# DAC_LED_Monitor.net
KiCad netlist of a schematic drawn in Altium Designer
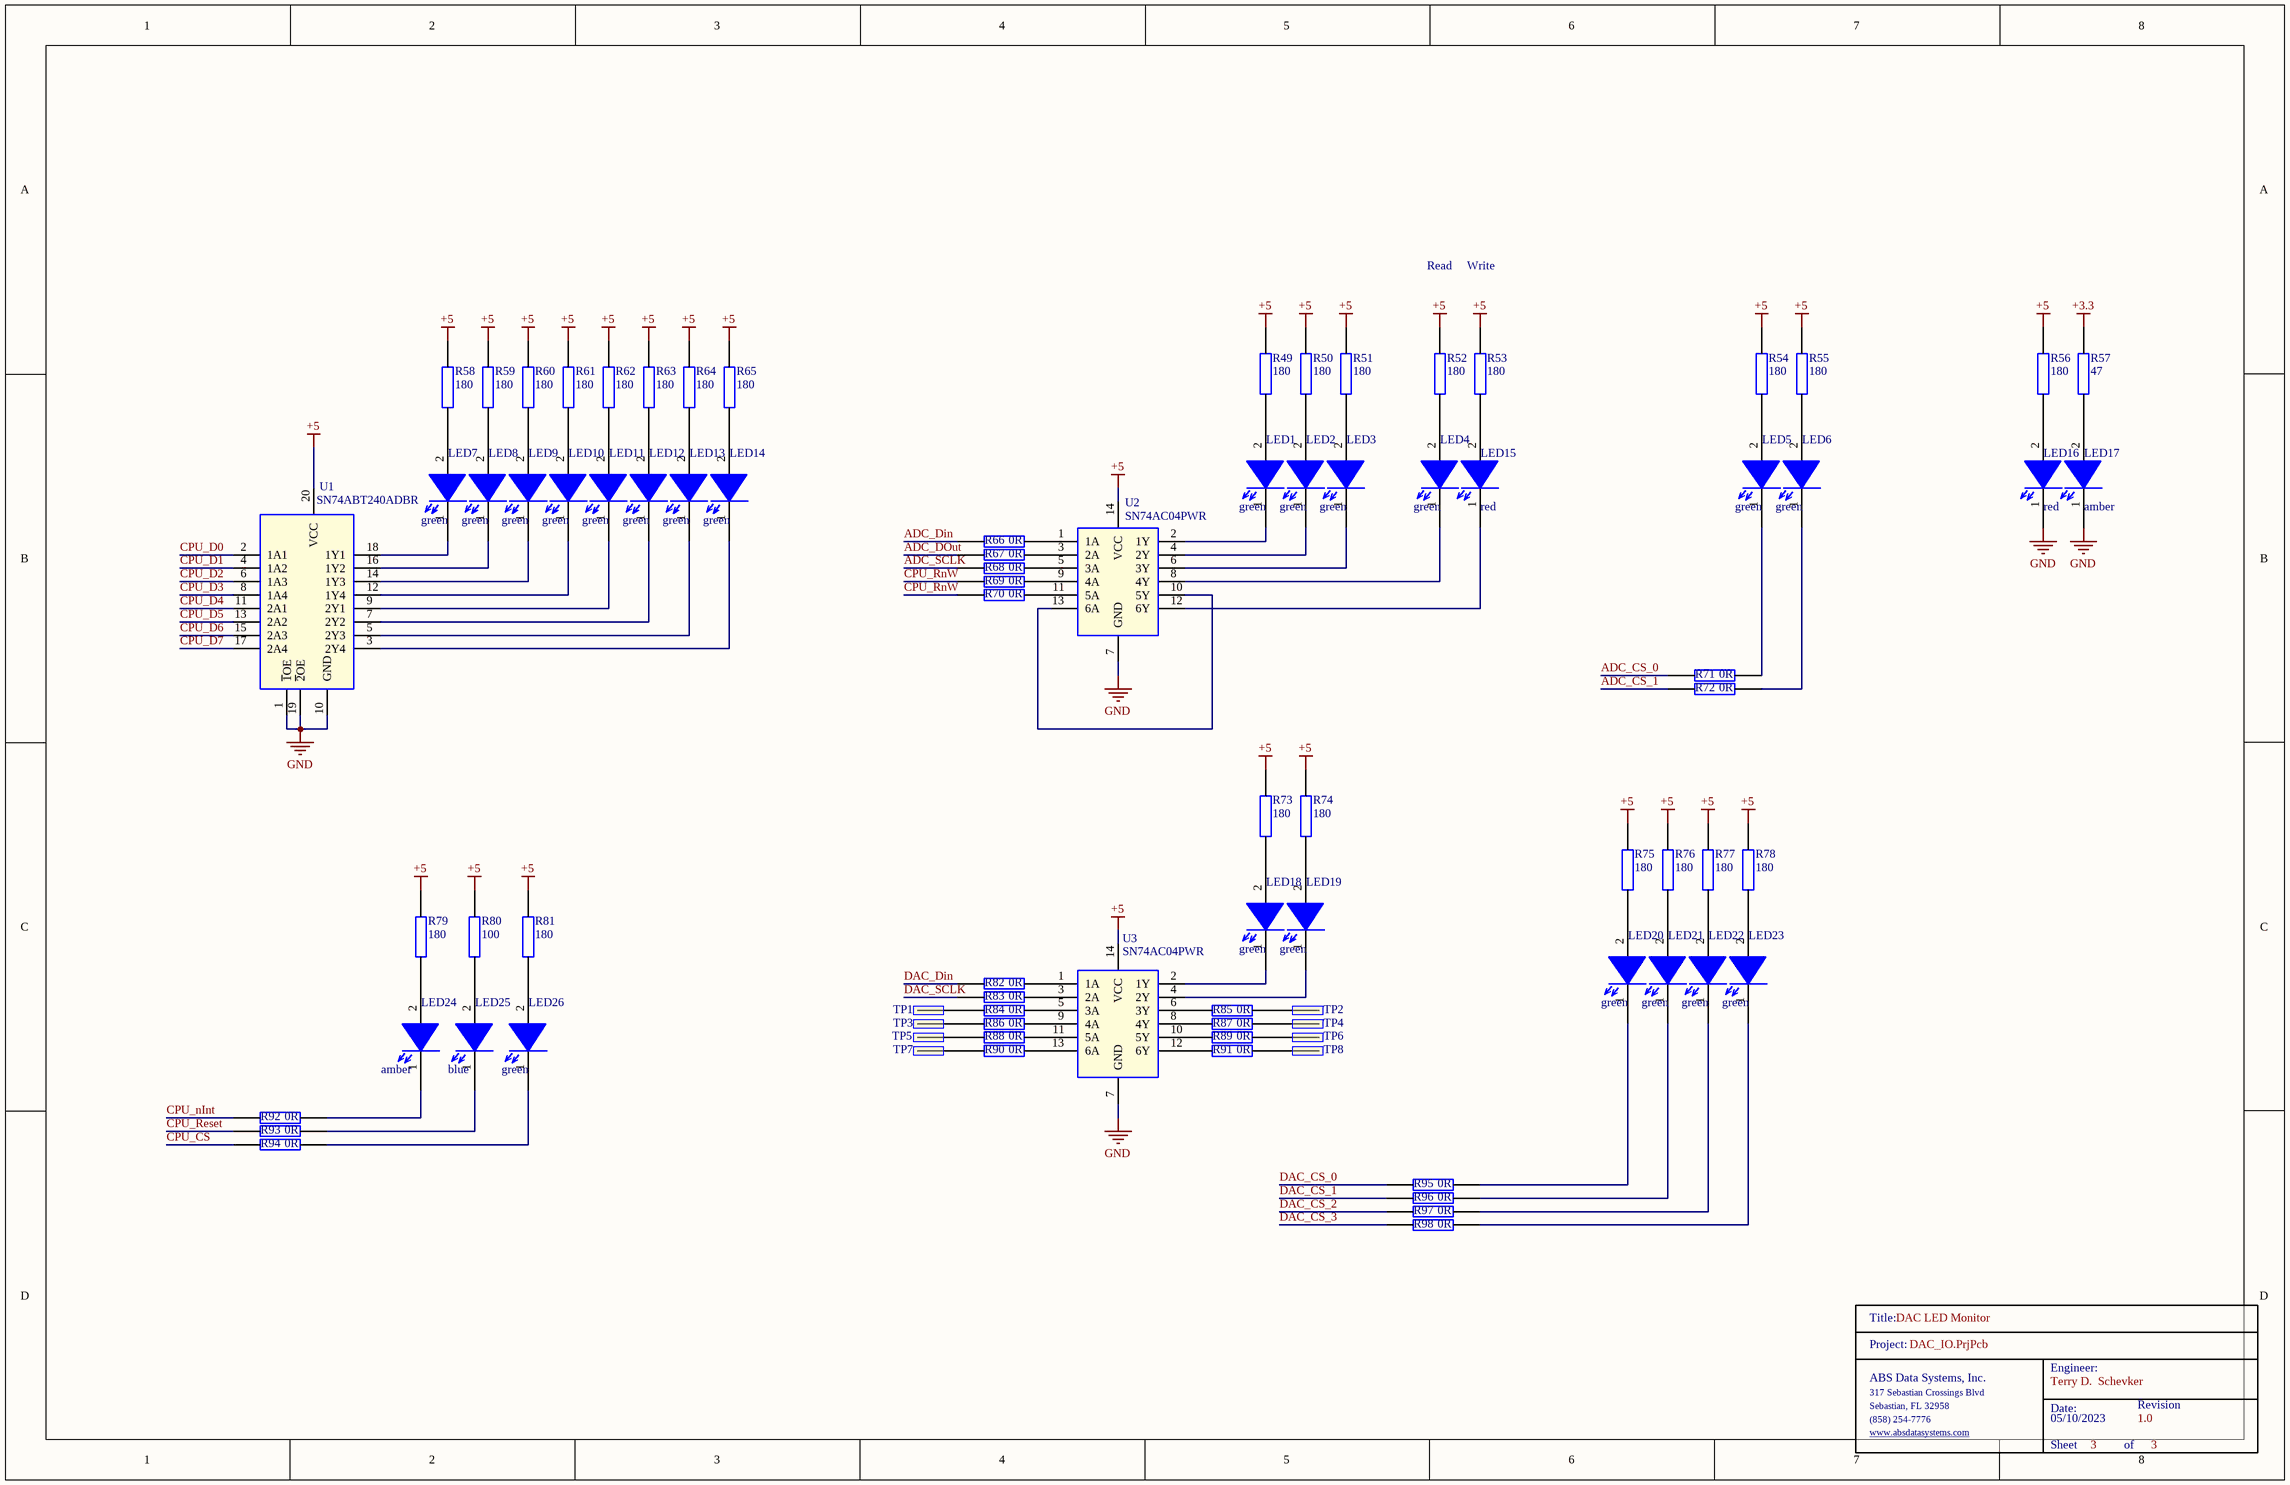
[diagram p0: DAC_LED_Monitor.SchDoc]

(export (version "E")
  (design (tool "Eeschema 10.0.6"))
  (components
    (comp (ref "LED1")
      (value "green")
      (footprint "0603_Diode")
      (description "Wurth Elektronik 0603 green")
      (fields
        (field (name "MANUFACTURER") "Wurth Electronics")
        (field (name "MANUFACTURER PART NUMBER") "150060GS75000")
      )
      (libsource (lib "Misc") (part "150060GS75000"))
    )
    (comp (ref "LED2")
      (value "green")
      (footprint "0603_Diode")
      (description "Wurth Elektronik 0603 green")
      (fields
        (field (name "MANUFACTURER") "Wurth Electronics")
        (field (name "MANUFACTURER PART NUMBER") "150060GS75000")
      )
      (libsource (lib "Misc") (part "150060GS75000"))
    )
    (comp (ref "LED3")
      (value "green")
      (footprint "0603_Diode")
      (description "Wurth Elektronik 0603 green")
      (fields
        (field (name "MANUFACTURER") "Wurth Electronics")
        (field (name "MANUFACTURER PART NUMBER") "150060GS75000")
      )
      (libsource (lib "Misc") (part "150060GS75000"))
    )
    (comp (ref "LED4")
      (value "green")
      (footprint "0603_Diode")
      (description "Wurth Elektronik 0603 green")
      (fields
        (field (name "MANUFACTURER") "Wurth Electronics")
        (field (name "MANUFACTURER PART NUMBER") "150060GS75000")
      )
      (libsource (lib "Misc") (part "150060GS75000"))
    )
    (comp (ref "LED5")
      (value "green")
      (footprint "0603_Diode")
      (description "Wurth Elektronik 0603 green")
      (fields
        (field (name "MANUFACTURER") "Wurth Electronics")
        (field (name "MANUFACTURER PART NUMBER") "150060GS75000")
      )
      (libsource (lib "Misc") (part "150060GS75000"))
    )
    (comp (ref "LED6")
      (value "green")
      (footprint "0603_Diode")
      (description "Wurth Elektronik 0603 green")
      (fields
        (field (name "MANUFACTURER") "Wurth Electronics")
        (field (name "MANUFACTURER PART NUMBER") "150060GS75000")
      )
      (libsource (lib "Misc") (part "150060GS75000"))
    )
    (comp (ref "LED7")
      (value "green")
      (footprint "0603_Diode")
      (description "Wurth Elektronik 0603 green")
      (fields
        (field (name "MANUFACTURER") "Wurth Electronics")
        (field (name "MANUFACTURER PART NUMBER") "150060GS75000")
      )
      (libsource (lib "Misc") (part "150060GS75000"))
    )
    (comp (ref "LED8")
      (value "green")
      (footprint "0603_Diode")
      (description "Wurth Elektronik 0603 green")
      (fields
        (field (name "MANUFACTURER") "Wurth Electronics")
        (field (name "MANUFACTURER PART NUMBER") "150060GS75000")
      )
      (libsource (lib "Misc") (part "150060GS75000"))
    )
    (comp (ref "LED9")
      (value "green")
      (footprint "0603_Diode")
      (description "Wurth Elektronik 0603 green")
      (fields
        (field (name "MANUFACTURER") "Wurth Electronics")
        (field (name "MANUFACTURER PART NUMBER") "150060GS75000")
      )
      (libsource (lib "Misc") (part "150060GS75000"))
    )
    (comp (ref "LED10")
      (value "green")
      (footprint "0603_Diode")
      (description "Wurth Elektronik 0603 green")
      (fields
        (field (name "MANUFACTURER") "Wurth Electronics")
        (field (name "MANUFACTURER PART NUMBER") "150060GS75000")
      )
      (libsource (lib "Misc") (part "150060GS75000"))
    )
    (comp (ref "LED11")
      (value "green")
      (footprint "0603_Diode")
      (description "Wurth Elektronik 0603 green")
      (fields
        (field (name "MANUFACTURER") "Wurth Electronics")
        (field (name "MANUFACTURER PART NUMBER") "150060GS75000")
      )
      (libsource (lib "Misc") (part "150060GS75000"))
    )
    (comp (ref "LED12")
      (value "green")
      (footprint "0603_Diode")
      (description "Wurth Elektronik 0603 green")
      (fields
        (field (name "MANUFACTURER") "Wurth Electronics")
        (field (name "MANUFACTURER PART NUMBER") "150060GS75000")
      )
      (libsource (lib "Misc") (part "150060GS75000"))
    )
    (comp (ref "LED13")
      (value "green")
      (footprint "0603_Diode")
      (description "Wurth Elektronik 0603 green")
      (fields
        (field (name "MANUFACTURER") "Wurth Electronics")
        (field (name "MANUFACTURER PART NUMBER") "150060GS75000")
      )
      (libsource (lib "Misc") (part "150060GS75000"))
    )
    (comp (ref "LED14")
      (value "green")
      (footprint "0603_Diode")
      (description "Wurth Elektronik 0603 green")
      (fields
        (field (name "MANUFACTURER") "Wurth Electronics")
        (field (name "MANUFACTURER PART NUMBER") "150060GS75000")
      )
      (libsource (lib "Misc") (part "150060GS75000"))
    )
    (comp (ref "LED15")
      (value "red")
      (footprint "0603_Diode")
      (description "Wurth Elektronik 0603 red")
      (fields
        (field (name "MANUFACTURER") "Wurth Electronics")
        (field (name "MANUFACTURER PART NUMBER") "150060GS75000")
      )
      (libsource (lib "Misc") (part "150060RS75000"))
    )
    (comp (ref "LED16")
      (value "red")
      (footprint "0603_Diode")
      (description "Wurth Elektronik 0603 red")
      (fields
        (field (name "MANUFACTURER") "Wurth Electronics")
        (field (name "MANUFACTURER PART NUMBER") "150060GS75000")
      )
      (libsource (lib "Misc") (part "150060RS75000"))
    )
    (comp (ref "LED17")
      (value "amber")
      (footprint "0603_Diode")
      (description "Wurth Elektronik 0603 amber")
      (fields
        (field (name "MANUFACTURER") "Wurth Electronics")
        (field (name "MANUFACTURER PART NUMBER") "150060GS75000")
      )
      (libsource (lib "Misc") (part "150060AS75000"))
    )
    (comp (ref "LED18")
      (value "green")
      (footprint "0603_Diode")
      (description "Wurth Elektronik 0603 green")
      (fields
        (field (name "MANUFACTURER") "Wurth Electronics")
        (field (name "MANUFACTURER PART NUMBER") "150060GS75000")
      )
      (libsource (lib "Misc") (part "150060GS75000"))
    )
    (comp (ref "LED19")
      (value "green")
      (footprint "0603_Diode")
      (description "Wurth Elektronik 0603 green")
      (fields
        (field (name "MANUFACTURER") "Wurth Electronics")
        (field (name "MANUFACTURER PART NUMBER") "150060GS75000")
      )
      (libsource (lib "Misc") (part "150060GS75000"))
    )
    (comp (ref "LED20")
      (value "green")
      (footprint "0603_Diode")
      (description "Wurth Elektronik 0603 green")
      (fields
        (field (name "MANUFACTURER") "Wurth Electronics")
        (field (name "MANUFACTURER PART NUMBER") "150060GS75000")
      )
      (libsource (lib "Misc") (part "150060GS75000"))
    )
    (comp (ref "LED21")
      (value "green")
      (footprint "0603_Diode")
      (description "Wurth Elektronik 0603 green")
      (fields
        (field (name "MANUFACTURER") "Wurth Electronics")
        (field (name "MANUFACTURER PART NUMBER") "150060GS75000")
      )
      (libsource (lib "Misc") (part "150060GS75000"))
    )
    (comp (ref "LED22")
      (value "green")
      (footprint "0603_Diode")
      (description "Wurth Elektronik 0603 green")
      (fields
        (field (name "MANUFACTURER") "Wurth Electronics")
        (field (name "MANUFACTURER PART NUMBER") "150060GS75000")
      )
      (libsource (lib "Misc") (part "150060GS75000"))
    )
    (comp (ref "LED23")
      (value "green")
      (footprint "0603_Diode")
      (description "Wurth Elektronik 0603 green")
      (fields
        (field (name "MANUFACTURER") "Wurth Electronics")
        (field (name "MANUFACTURER PART NUMBER") "150060GS75000")
      )
      (libsource (lib "Misc") (part "150060GS75000"))
    )
    (comp (ref "LED24")
      (value "amber")
      (footprint "0603_Diode")
      (description "Wurth Elektronik 0603 amber")
      (fields
        (field (name "MANUFACTURER") "Wurth Electronics")
        (field (name "MANUFACTURER PART NUMBER") "150060GS75000")
      )
      (libsource (lib "Misc") (part "150060AS75000"))
    )
    (comp (ref "LED25")
      (value "blue")
      (footprint "0603_Diode")
      (description "Wurth Elektronik 0603 blue")
      (fields
        (field (name "MANUFACTURER") "Wurth Electronics")
        (field (name "MANUFACTURER PART NUMBER") "150060GS75000")
      )
      (libsource (lib "Misc") (part "150060BS75000"))
    )
    (comp (ref "LED26")
      (value "green")
      (footprint "0603_Diode")
      (description "Wurth Elektronik 0603 green")
      (fields
        (field (name "MANUFACTURER") "Wurth Electronics")
        (field (name "MANUFACTURER PART NUMBER") "150060GS75000")
      )
      (libsource (lib "Misc") (part "150060GS75000"))
    )
    (comp (ref "R49")
      (value "180")
      (footprint "0603")
      (description "YAGEO 0603 180 ohm")
      (fields
        (field (name "MOUSER PART NUMBER") "603-RC0603JR-070RL")
        (field (name "MANUFACTURER_PART_NUMBER") "RC0603JR-070RL")
      )
      (libsource (lib "Resistors") (part "RC0603FR-13180RL"))
    )
    (comp (ref "R50")
      (value "180")
      (footprint "0603")
      (description "YAGEO 0603 180 ohm")
      (fields
        (field (name "MOUSER PART NUMBER") "603-RC0603JR-070RL")
        (field (name "MANUFACTURER_PART_NUMBER") "RC0603JR-070RL")
      )
      (libsource (lib "Resistors") (part "RC0603FR-13180RL"))
    )
    (comp (ref "R51")
      (value "180")
      (footprint "0603")
      (description "YAGEO 0603 180 ohm")
      (fields
        (field (name "MOUSER PART NUMBER") "603-RC0603JR-070RL")
        (field (name "MANUFACTURER_PART_NUMBER") "RC0603JR-070RL")
      )
      (libsource (lib "Resistors") (part "RC0603FR-13180RL"))
    )
    (comp (ref "R52")
      (value "180")
      (footprint "0603")
      (description "YAGEO 0603 180 ohm")
      (fields
        (field (name "MOUSER PART NUMBER") "603-RC0603JR-070RL")
        (field (name "MANUFACTURER_PART_NUMBER") "RC0603JR-070RL")
      )
      (libsource (lib "Resistors") (part "RC0603FR-13180RL"))
    )
    (comp (ref "R53")
      (value "180")
      (footprint "0603")
      (description "YAGEO 0603 180 ohm")
      (fields
        (field (name "MOUSER PART NUMBER") "603-RC0603JR-070RL")
        (field (name "MANUFACTURER_PART_NUMBER") "RC0603JR-070RL")
      )
      (libsource (lib "Resistors") (part "RC0603FR-13180RL"))
    )
    (comp (ref "R54")
      (value "180")
      (footprint "0603")
      (description "YAGEO 0603 180 ohm")
      (fields
        (field (name "MOUSER PART NUMBER") "603-RC0603JR-070RL")
        (field (name "MANUFACTURER_PART_NUMBER") "RC0603JR-070RL")
      )
      (libsource (lib "Resistors") (part "RC0603FR-13180RL"))
    )
    (comp (ref "R55")
      (value "180")
      (footprint "0603")
      (description "YAGEO 0603 180 ohm")
      (fields
        (field (name "MOUSER PART NUMBER") "603-RC0603JR-070RL")
        (field (name "MANUFACTURER_PART_NUMBER") "RC0603JR-070RL")
      )
      (libsource (lib "Resistors") (part "RC0603FR-13180RL"))
    )
    (comp (ref "R56")
      (value "180")
      (footprint "0603")
      (description "YAGEO 0603 180 ohm")
      (fields
        (field (name "MOUSER PART NUMBER") "603-RC0603JR-070RL")
        (field (name "MANUFACTURER_PART_NUMBER") "RC0603JR-070RL")
      )
      (libsource (lib "Resistors") (part "RC0603FR-13180RL"))
    )
    (comp (ref "R57")
      (value "47")
      (footprint "0603")
      (description "YAGEO 0603 47")
      (fields
        (field (name "MOUSER PART NUMBER") "603-RC0603JR-070RL")
        (field (name "MANUFACTURER_PART_NUMBER") "RC0603JR-070RL")
      )
      (libsource (lib "Resistors") (part "RC0603FR-0747KL"))
    )
    (comp (ref "R58")
      (value "180")
      (footprint "0603")
      (description "YAGEO 0603 180 ohm")
      (fields
        (field (name "MOUSER PART NUMBER") "603-RC0603JR-070RL")
        (field (name "MANUFACTURER_PART_NUMBER") "RC0603JR-070RL")
      )
      (libsource (lib "Resistors") (part "RC0603FR-13180RL"))
    )
    (comp (ref "R59")
      (value "180")
      (footprint "0603")
      (description "YAGEO 0603 180 ohm")
      (fields
        (field (name "MOUSER PART NUMBER") "603-RC0603JR-070RL")
        (field (name "MANUFACTURER_PART_NUMBER") "RC0603JR-070RL")
      )
      (libsource (lib "Resistors") (part "RC0603FR-13180RL"))
    )
    (comp (ref "R60")
      (value "180")
      (footprint "0603")
      (description "YAGEO 0603 180 ohm")
      (fields
        (field (name "MOUSER PART NUMBER") "603-RC0603JR-070RL")
        (field (name "MANUFACTURER_PART_NUMBER") "RC0603JR-070RL")
      )
      (libsource (lib "Resistors") (part "RC0603FR-13180RL"))
    )
    (comp (ref "R61")
      (value "180")
      (footprint "0603")
      (description "YAGEO 0603 180 ohm")
      (fields
        (field (name "MOUSER PART NUMBER") "603-RC0603JR-070RL")
        (field (name "MANUFACTURER_PART_NUMBER") "RC0603JR-070RL")
      )
      (libsource (lib "Resistors") (part "RC0603FR-13180RL"))
    )
    (comp (ref "R62")
      (value "180")
      (footprint "0603")
      (description "YAGEO 0603 180 ohm")
      (fields
        (field (name "MOUSER PART NUMBER") "603-RC0603JR-070RL")
        (field (name "MANUFACTURER_PART_NUMBER") "RC0603JR-070RL")
      )
      (libsource (lib "Resistors") (part "RC0603FR-13180RL"))
    )
    (comp (ref "R63")
      (value "180")
      (footprint "0603")
      (description "YAGEO 0603 180 ohm")
      (fields
        (field (name "MOUSER PART NUMBER") "603-RC0603JR-070RL")
        (field (name "MANUFACTURER_PART_NUMBER") "RC0603JR-070RL")
      )
      (libsource (lib "Resistors") (part "RC0603FR-13180RL"))
    )
    (comp (ref "R64")
      (value "180")
      (footprint "0603")
      (description "YAGEO 0603 180 ohm")
      (fields
        (field (name "MOUSER PART NUMBER") "603-RC0603JR-070RL")
        (field (name "MANUFACTURER_PART_NUMBER") "RC0603JR-070RL")
      )
      (libsource (lib "Resistors") (part "RC0603FR-13180RL"))
    )
    (comp (ref "R65")
      (value "180")
      (footprint "0603")
      (description "YAGEO 0603 180 ohm")
      (fields
        (field (name "MOUSER PART NUMBER") "603-RC0603JR-070RL")
        (field (name "MANUFACTURER_PART_NUMBER") "RC0603JR-070RL")
      )
      (libsource (lib "Resistors") (part "RC0603FR-13180RL"))
    )
    (comp (ref "R66")
      (value "0R")
      (footprint "0603")
      (description "YAGEO 0603 0 ohm")
      (fields
        (field (name "MOUSER PART NUMBER") "603-RC0603JR-070RL")
        (field (name "MANUFACTURER_PART_NUMBER") "RC0603JR-070RL")
      )
      (libsource (lib "Resistors") (part "RC0603JR-070RL"))
    )
    (comp (ref "R67")
      (value "0R")
      (footprint "0603")
      (description "YAGEO 0603 0 ohm")
      (fields
        (field (name "MOUSER PART NUMBER") "603-RC0603JR-070RL")
        (field (name "MANUFACTURER_PART_NUMBER") "RC0603JR-070RL")
      )
      (libsource (lib "Resistors") (part "RC0603JR-070RL"))
    )
    (comp (ref "R68")
      (value "0R")
      (footprint "0603")
      (description "YAGEO 0603 0 ohm")
      (fields
        (field (name "MOUSER PART NUMBER") "603-RC0603JR-070RL")
        (field (name "MANUFACTURER_PART_NUMBER") "RC0603JR-070RL")
      )
      (libsource (lib "Resistors") (part "RC0603JR-070RL"))
    )
    (comp (ref "R69")
      (value "0R")
      (footprint "0603")
      (description "YAGEO 0603 0 ohm")
      (fields
        (field (name "MOUSER PART NUMBER") "603-RC0603JR-070RL")
        (field (name "MANUFACTURER_PART_NUMBER") "RC0603JR-070RL")
      )
      (libsource (lib "Resistors") (part "RC0603JR-070RL"))
    )
    (comp (ref "R70")
      (value "0R")
      (footprint "0603")
      (description "YAGEO 0603 0 ohm")
      (fields
        (field (name "MOUSER PART NUMBER") "603-RC0603JR-070RL")
        (field (name "MANUFACTURER_PART_NUMBER") "RC0603JR-070RL")
      )
      (libsource (lib "Resistors") (part "RC0603JR-070RL"))
    )
    (comp (ref "R71")
      (value "0R")
      (footprint "0603")
      (description "YAGEO 0603 0 ohm")
      (fields
        (field (name "MOUSER PART NUMBER") "603-RC0603JR-070RL")
        (field (name "MANUFACTURER_PART_NUMBER") "RC0603JR-070RL")
      )
      (libsource (lib "Resistors") (part "RC0603JR-070RL"))
    )
    (comp (ref "R72")
      (value "0R")
      (footprint "0603")
      (description "YAGEO 0603 0 ohm")
      (fields
        (field (name "MOUSER PART NUMBER") "603-RC0603JR-070RL")
        (field (name "MANUFACTURER_PART_NUMBER") "RC0603JR-070RL")
      )
      (libsource (lib "Resistors") (part "RC0603JR-070RL"))
    )
    (comp (ref "R73")
      (value "180")
      (footprint "0603")
      (description "YAGEO 0603 180 ohm")
      (fields
        (field (name "MOUSER PART NUMBER") "603-RC0603JR-070RL")
        (field (name "MANUFACTURER_PART_NUMBER") "RC0603JR-070RL")
      )
      (libsource (lib "Resistors") (part "RC0603FR-13180RL"))
    )
    (comp (ref "R74")
      (value "180")
      (footprint "0603")
      (description "YAGEO 0603 180 ohm")
      (fields
        (field (name "MOUSER PART NUMBER") "603-RC0603JR-070RL")
        (field (name "MANUFACTURER_PART_NUMBER") "RC0603JR-070RL")
      )
      (libsource (lib "Resistors") (part "RC0603FR-13180RL"))
    )
    (comp (ref "R75")
      (value "180")
      (footprint "0603")
      (description "YAGEO 0603 180 ohm")
      (fields
        (field (name "MOUSER PART NUMBER") "603-RC0603JR-070RL")
        (field (name "MANUFACTURER_PART_NUMBER") "RC0603JR-070RL")
      )
      (libsource (lib "Resistors") (part "RC0603FR-13180RL"))
    )
    (comp (ref "R76")
      (value "180")
      (footprint "0603")
      (description "YAGEO 0603 180 ohm")
      (fields
        (field (name "MOUSER PART NUMBER") "603-RC0603JR-070RL")
        (field (name "MANUFACTURER_PART_NUMBER") "RC0603JR-070RL")
      )
      (libsource (lib "Resistors") (part "RC0603FR-13180RL"))
    )
    (comp (ref "R77")
      (value "180")
      (footprint "0603")
      (description "YAGEO 0603 180 ohm")
      (fields
        (field (name "MOUSER PART NUMBER") "603-RC0603JR-070RL")
        (field (name "MANUFACTURER_PART_NUMBER") "RC0603JR-070RL")
      )
      (libsource (lib "Resistors") (part "RC0603FR-13180RL"))
    )
    (comp (ref "R78")
      (value "180")
      (footprint "0603")
      (description "YAGEO 0603 180 ohm")
      (fields
        (field (name "MOUSER PART NUMBER") "603-RC0603JR-070RL")
        (field (name "MANUFACTURER_PART_NUMBER") "RC0603JR-070RL")
      )
      (libsource (lib "Resistors") (part "RC0603FR-13180RL"))
    )
    (comp (ref "R79")
      (value "180")
      (footprint "0603")
      (description "YAGEO 0603 180 ohm")
      (fields
        (field (name "MOUSER PART NUMBER") "603-RC0603JR-070RL")
        (field (name "MANUFACTURER_PART_NUMBER") "RC0603JR-070RL")
      )
      (libsource (lib "Resistors") (part "RC0603FR-13180RL"))
    )
    (comp (ref "R80")
      (value "100")
      (footprint "0603")
      (description "YAGEO 0603 100 ohm")
      (fields
        (field (name "MOUSER PART NUMBER") "603-RC0603JR-070RL")
        (field (name "MANUFACTURER_PART_NUMBER") "RC0603JR-070RL")
      )
      (libsource (lib "Resistors") (part "RC0603FR-10100RL"))
    )
    (comp (ref "R81")
      (value "180")
      (footprint "0603")
      (description "YAGEO 0603 180 ohm")
      (fields
        (field (name "MOUSER PART NUMBER") "603-RC0603JR-070RL")
        (field (name "MANUFACTURER_PART_NUMBER") "RC0603JR-070RL")
      )
      (libsource (lib "Resistors") (part "RC0603FR-13180RL"))
    )
    (comp (ref "R82")
      (value "0R")
      (footprint "0603")
      (description "YAGEO 0603 0 ohm")
      (fields
        (field (name "MOUSER PART NUMBER") "603-RC0603JR-070RL")
        (field (name "MANUFACTURER_PART_NUMBER") "RC0603JR-070RL")
      )
      (libsource (lib "Resistors") (part "RC0603JR-070RL"))
    )
    (comp (ref "R83")
      (value "0R")
      (footprint "0603")
      (description "YAGEO 0603 0 ohm")
      (fields
        (field (name "MOUSER PART NUMBER") "603-RC0603JR-070RL")
        (field (name "MANUFACTURER_PART_NUMBER") "RC0603JR-070RL")
      )
      (libsource (lib "Resistors") (part "RC0603JR-070RL"))
    )
    (comp (ref "R84")
      (value "0R")
      (footprint "0603")
      (description "YAGEO 0603 0 ohm")
      (fields
        (field (name "MOUSER PART NUMBER") "603-RC0603JR-070RL")
        (field (name "MANUFACTURER_PART_NUMBER") "RC0603JR-070RL")
      )
      (libsource (lib "Resistors") (part "RC0603JR-070RL"))
    )
    (comp (ref "R85")
      (value "0R")
      (footprint "0603")
      (description "YAGEO 0603 0 ohm")
      (fields
        (field (name "MOUSER PART NUMBER") "603-RC0603JR-070RL")
        (field (name "MANUFACTURER_PART_NUMBER") "RC0603JR-070RL")
      )
      (libsource (lib "Resistors") (part "RC0603JR-070RL"))
    )
    (comp (ref "R86")
      (value "0R")
      (footprint "0603")
      (description "YAGEO 0603 0 ohm")
      (fields
        (field (name "MOUSER PART NUMBER") "603-RC0603JR-070RL")
        (field (name "MANUFACTURER_PART_NUMBER") "RC0603JR-070RL")
      )
      (libsource (lib "Resistors") (part "RC0603JR-070RL"))
    )
    (comp (ref "R87")
      (value "0R")
      (footprint "0603")
      (description "YAGEO 0603 0 ohm")
      (fields
        (field (name "MOUSER PART NUMBER") "603-RC0603JR-070RL")
        (field (name "MANUFACTURER_PART_NUMBER") "RC0603JR-070RL")
      )
      (libsource (lib "Resistors") (part "RC0603JR-070RL"))
    )
    (comp (ref "R88")
      (value "0R")
      (footprint "0603")
      (description "YAGEO 0603 0 ohm")
      (fields
        (field (name "MOUSER PART NUMBER") "603-RC0603JR-070RL")
        (field (name "MANUFACTURER_PART_NUMBER") "RC0603JR-070RL")
      )
      (libsource (lib "Resistors") (part "RC0603JR-070RL"))
    )
    (comp (ref "R89")
      (value "0R")
      (footprint "0603")
      (description "YAGEO 0603 0 ohm")
      (fields
        (field (name "MOUSER PART NUMBER") "603-RC0603JR-070RL")
        (field (name "MANUFACTURER_PART_NUMBER") "RC0603JR-070RL")
      )
      (libsource (lib "Resistors") (part "RC0603JR-070RL"))
    )
    (comp (ref "R90")
      (value "0R")
      (footprint "0603")
      (description "YAGEO 0603 0 ohm")
      (fields
        (field (name "MOUSER PART NUMBER") "603-RC0603JR-070RL")
        (field (name "MANUFACTURER_PART_NUMBER") "RC0603JR-070RL")
      )
      (libsource (lib "Resistors") (part "RC0603JR-070RL"))
    )
    (comp (ref "R91")
      (value "0R")
      (footprint "0603")
      (description "YAGEO 0603 0 ohm")
      (fields
        (field (name "MOUSER PART NUMBER") "603-RC0603JR-070RL")
        (field (name "MANUFACTURER_PART_NUMBER") "RC0603JR-070RL")
      )
      (libsource (lib "Resistors") (part "RC0603JR-070RL"))
    )
    (comp (ref "R92")
      (value "0R")
      (footprint "0603")
      (description "YAGEO 0603 0 ohm")
      (fields
        (field (name "MOUSER PART NUMBER") "603-RC0603JR-070RL")
        (field (name "MANUFACTURER_PART_NUMBER") "RC0603JR-070RL")
      )
      (libsource (lib "Resistors") (part "RC0603JR-070RL"))
    )
    (comp (ref "R93")
      (value "0R")
      (footprint "0603")
      (description "YAGEO 0603 0 ohm")
      (fields
        (field (name "MOUSER PART NUMBER") "603-RC0603JR-070RL")
        (field (name "MANUFACTURER_PART_NUMBER") "RC0603JR-070RL")
      )
      (libsource (lib "Resistors") (part "RC0603JR-070RL"))
    )
    (comp (ref "R94")
      (value "0R")
      (footprint "0603")
      (description "YAGEO 0603 0 ohm")
      (fields
        (field (name "MOUSER PART NUMBER") "603-RC0603JR-070RL")
        (field (name "MANUFACTURER_PART_NUMBER") "RC0603JR-070RL")
      )
      (libsource (lib "Resistors") (part "RC0603JR-070RL"))
    )
    (comp (ref "R95")
      (value "0R")
      (footprint "0603")
      (description "YAGEO 0603 0 ohm")
      (fields
        (field (name "MOUSER PART NUMBER") "603-RC0603JR-070RL")
        (field (name "MANUFACTURER_PART_NUMBER") "RC0603JR-070RL")
      )
      (libsource (lib "Resistors") (part "RC0603JR-070RL"))
    )
    (comp (ref "R96")
      (value "0R")
      (footprint "0603")
      (description "YAGEO 0603 0 ohm")
      (fields
        (field (name "MOUSER PART NUMBER") "603-RC0603JR-070RL")
        (field (name "MANUFACTURER_PART_NUMBER") "RC0603JR-070RL")
      )
      (libsource (lib "Resistors") (part "RC0603JR-070RL"))
    )
    (comp (ref "R97")
      (value "0R")
      (footprint "0603")
      (description "YAGEO 0603 0 ohm")
      (fields
        (field (name "MOUSER PART NUMBER") "603-RC0603JR-070RL")
        (field (name "MANUFACTURER_PART_NUMBER") "RC0603JR-070RL")
      )
      (libsource (lib "Resistors") (part "RC0603JR-070RL"))
    )
    (comp (ref "R98")
      (value "0R")
      (footprint "0603")
      (description "YAGEO 0603 0 ohm")
      (fields
        (field (name "MOUSER PART NUMBER") "603-RC0603JR-070RL")
        (field (name "MANUFACTURER_PART_NUMBER") "RC0603JR-070RL")
      )
      (libsource (lib "Resistors") (part "RC0603JR-070RL"))
    )
    (comp (ref "TitleBlock_2") (value "TitleBlock") (libsource (lib "Misc") (part "TitleBlock")))
    (comp (ref "TP1")
      (value "TP")
      (footprint "TP")
      (fields
        (field (name "MANUFACTURER") "Samtec")
        (field (name "MANUFACTURER PART NUMBER") "TST-105-01-G-D")
      )
      (libsource (lib "") (part "TP_1"))
    )
    (comp (ref "TP2")
      (value "TP")
      (footprint "TP")
      (fields
        (field (name "MANUFACTURER") "Samtec")
        (field (name "MANUFACTURER PART NUMBER") "TST-105-01-G-D")
      )
      (libsource (lib "Misc") (part "TP"))
    )
    (comp (ref "TP3")
      (value "TP")
      (footprint "TP")
      (fields
        (field (name "MANUFACTURER") "Samtec")
        (field (name "MANUFACTURER PART NUMBER") "TST-105-01-G-D")
      )
      (libsource (lib "") (part "TP_1"))
    )
    (comp (ref "TP4")
      (value "TP")
      (footprint "TP")
      (fields
        (field (name "MANUFACTURER") "Samtec")
        (field (name "MANUFACTURER PART NUMBER") "TST-105-01-G-D")
      )
      (libsource (lib "Misc") (part "TP"))
    )
    (comp (ref "TP5")
      (value "TP")
      (footprint "TP")
      (fields
        (field (name "MANUFACTURER") "Samtec")
        (field (name "MANUFACTURER PART NUMBER") "TST-105-01-G-D")
      )
      (libsource (lib "") (part "TP_1"))
    )
    (comp (ref "TP6")
      (value "TP")
      (footprint "TP")
      (fields
        (field (name "MANUFACTURER") "Samtec")
        (field (name "MANUFACTURER PART NUMBER") "TST-105-01-G-D")
      )
      (libsource (lib "Misc") (part "TP"))
    )
    (comp (ref "TP7")
      (value "TP")
      (footprint "TP")
      (fields
        (field (name "MANUFACTURER") "Samtec")
        (field (name "MANUFACTURER PART NUMBER") "TST-105-01-G-D")
      )
      (libsource (lib "") (part "TP_1"))
    )
    (comp (ref "TP8")
      (value "TP")
      (footprint "TP")
      (fields
        (field (name "MANUFACTURER") "Samtec")
        (field (name "MANUFACTURER PART NUMBER") "TST-105-01-G-D")
      )
      (libsource (lib "Misc") (part "TP"))
    )
    (comp (ref "U1")
      (value "SN74ABT240ADBR")
      (footprint "SOP65P780X200-20N")
      (description "Octal Buffers/Drivers With 3-State Outputs")
      (fields (field (name "MOUSER PART NUMBER") "595-SN74ABT240ADBR"))
      (libsource (lib "Logic") (part "SN74ABT240ADBR"))
    )
    (comp (ref "U2")
      (value "SN74AC04PWR")
      (footprint "SOP65P640X120-14N")
      (description "Hex Inverters")
      (fields (field (name "MOUSER PART NUMBER") "595-SN74AC04PWR"))
      (libsource (lib "Logic") (part "SN74AC04PWR"))
    )
    (comp (ref "U3")
      (value "SN74AC04PWR")
      (footprint "SOP65P640X120-14N")
      (description "Hex Inverters")
      (fields (field (name "MOUSER PART NUMBER") "595-SN74AC04PWR"))
      (libsource (lib "Logic") (part "SN74AC04PWR"))
    )
  )
  (nets
    (net (code "1") (name "+3.3") (class "Default")
      (node (ref "R57") (pin "1") (pinfunction "1_1") (pintype "passive"))
    )
    (net (code "2") (name "+5") (class "Default")
      (node (ref "R49") (pin "2") (pinfunction "2_2") (pintype "passive"))
      (node (ref "R50") (pin "2") (pinfunction "2_2") (pintype "passive"))
      (node (ref "R51") (pin "2") (pinfunction "2_2") (pintype "passive"))
      (node (ref "R52") (pin "2") (pinfunction "2_2") (pintype "passive"))
      (node (ref "R53") (pin "2") (pinfunction "2_2") (pintype "passive"))
      (node (ref "R54") (pin "2") (pinfunction "2_2") (pintype "passive"))
      (node (ref "R55") (pin "2") (pinfunction "2_2") (pintype "passive"))
      (node (ref "R56") (pin "2") (pinfunction "2_2") (pintype "passive"))
      (node (ref "R58") (pin "2") (pinfunction "2_2") (pintype "passive"))
      (node (ref "R59") (pin "2") (pinfunction "2_2") (pintype "passive"))
      (node (ref "R60") (pin "2") (pinfunction "2_2") (pintype "passive"))
      (node (ref "R61") (pin "2") (pinfunction "2_2") (pintype "passive"))
      (node (ref "R62") (pin "2") (pinfunction "2_2") (pintype "passive"))
      (node (ref "R63") (pin "2") (pinfunction "2_2") (pintype "passive"))
      (node (ref "R64") (pin "2") (pinfunction "2_2") (pintype "passive"))
      (node (ref "R65") (pin "2") (pinfunction "2_2") (pintype "passive"))
      (node (ref "R73") (pin "2") (pinfunction "2_2") (pintype "passive"))
      (node (ref "R74") (pin "2") (pinfunction "2_2") (pintype "passive"))
      (node (ref "R75") (pin "2") (pinfunction "2_2") (pintype "passive"))
      (node (ref "R76") (pin "2") (pinfunction "2_2") (pintype "passive"))
      (node (ref "R77") (pin "2") (pinfunction "2_2") (pintype "passive"))
      (node (ref "R78") (pin "2") (pinfunction "2_2") (pintype "passive"))
      (node (ref "R79") (pin "2") (pinfunction "2_2") (pintype "passive"))
      (node (ref "R80") (pin "1") (pinfunction "1_1") (pintype "passive"))
      (node (ref "R81") (pin "2") (pinfunction "2_2") (pintype "passive"))
      (node (ref "U1") (pin "20") (pinfunction "VCC_20") (pintype "passive"))
      (node (ref "U2") (pin "14") (pinfunction "VCC_14") (pintype "passive"))
      (node (ref "U3") (pin "14") (pinfunction "VCC_14") (pintype "passive"))
    )
    (net (code "3") (name "/ADC_CS_0") (class "Default")
      (node (ref "R71") (pin "1") (pinfunction "1_1") (pintype "passive"))
    )
    (net (code "4") (name "/ADC_CS_1") (class "Default")
      (node (ref "R72") (pin "1") (pinfunction "1_1") (pintype "passive"))
    )
    (net (code "5") (name "/ADC_DOut") (class "Default")
      (node (ref "R67") (pin "1") (pinfunction "1_1") (pintype "passive"))
    )
    (net (code "6") (name "/ADC_Din") (class "Default")
      (node (ref "R66") (pin "1") (pinfunction "1_1") (pintype "passive"))
    )
    (net (code "7") (name "/ADC_SCLK") (class "Default")
      (node (ref "R68") (pin "1") (pinfunction "1_1") (pintype "passive"))
    )
    (net (code "8") (name "/CPU_CS") (class "Default")
      (node (ref "R94") (pin "1") (pinfunction "1_1") (pintype "passive"))
    )
    (net (code "9") (name "/CPU_D0") (class "Default")
      (node (ref "U1") (pin "2") (pinfunction "1A1_2") (pintype "passive"))
    )
    (net (code "10") (name "/CPU_D1") (class "Default")
      (node (ref "U1") (pin "4") (pinfunction "1A2_4") (pintype "passive"))
    )
    (net (code "11") (name "/CPU_D2") (class "Default")
      (node (ref "U1") (pin "6") (pinfunction "1A3_6") (pintype "passive"))
    )
    (net (code "12") (name "/CPU_D3") (class "Default")
      (node (ref "U1") (pin "8") (pinfunction "1A4_8") (pintype "passive"))
    )
    (net (code "13") (name "/CPU_D4") (class "Default")
      (node (ref "U1") (pin "11") (pinfunction "2A1_11") (pintype "passive"))
    )
    (net (code "14") (name "/CPU_D5") (class "Default")
      (node (ref "U1") (pin "13") (pinfunction "2A2_13") (pintype "passive"))
    )
    (net (code "15") (name "/CPU_D6") (class "Default")
      (node (ref "U1") (pin "15") (pinfunction "2A3_15") (pintype "passive"))
    )
    (net (code "16") (name "/CPU_D7") (class "Default")
      (node (ref "U1") (pin "17") (pinfunction "2A4_17") (pintype "passive"))
    )
    (net (code "17") (name "/CPU_Reset") (class "Default")
      (node (ref "R93") (pin "1") (pinfunction "1_1") (pintype "passive"))
    )
    (net (code "18") (name "/CPU_RnW") (class "Default")
      (node (ref "R69") (pin "1") (pinfunction "1_1") (pintype "passive"))
      (node (ref "R70") (pin "1") (pinfunction "1_1") (pintype "passive"))
    )
    (net (code "19") (name "/CPU_nInt") (class "Default")
      (node (ref "R92") (pin "1") (pinfunction "1_1") (pintype "passive"))
    )
    (net (code "20") (name "/DAC_CS_0") (class "Default")
      (node (ref "R95") (pin "1") (pinfunction "1_1") (pintype "passive"))
    )
    (net (code "21") (name "/DAC_CS_1") (class "Default")
      (node (ref "R96") (pin "1") (pinfunction "1_1") (pintype "passive"))
    )
    (net (code "22") (name "/DAC_CS_2") (class "Default")
      (node (ref "R97") (pin "1") (pinfunction "1_1") (pintype "passive"))
    )
    (net (code "23") (name "/DAC_CS_3") (class "Default")
      (node (ref "R98") (pin "1") (pinfunction "1_1") (pintype "passive"))
    )
    (net (code "24") (name "/DAC_Din") (class "Default")
      (node (ref "R82") (pin "1") (pinfunction "1_1") (pintype "passive"))
    )
    (net (code "25") (name "/DAC_SCLK") (class "Default")
      (node (ref "R83") (pin "1") (pinfunction "1_1") (pintype "passive"))
    )
    (net (code "26") (name "GND") (class "Default")
      (node (ref "LED16") (pin "1") (pinfunction "K_1") (pintype "passive"))
      (node (ref "LED17") (pin "1") (pinfunction "K_1") (pintype "passive"))
      (node (ref "U1") (pin "1") (pinfunction "~{1}OE_1") (pintype "passive"))
      (node (ref "U1") (pin "10") (pinfunction "GND_10") (pintype "passive"))
      (node (ref "U1") (pin "19") (pinfunction "~{2}OE_19") (pintype "passive"))
      (node (ref "U2") (pin "7") (pinfunction "GND_7") (pintype "passive"))
      (node (ref "U3") (pin "7") (pinfunction "GND_7") (pintype "passive"))
    )
    (net (code "27") (name "Net-(LED1-A)") (class "Default")
      (node (ref "LED1") (pin "2") (pinfunction "A_2") (pintype "passive"))
      (node (ref "R49") (pin "1") (pinfunction "1_1") (pintype "passive"))
    )
    (net (code "28") (name "Net-(LED1-K)") (class "Default")
      (node (ref "LED1") (pin "1") (pinfunction "K_1") (pintype "passive"))
      (node (ref "U2") (pin "2") (pinfunction "1Y_2") (pintype "passive"))
    )
    (net (code "29") (name "Net-(LED2-A)") (class "Default")
      (node (ref "LED2") (pin "2") (pinfunction "A_2") (pintype "passive"))
      (node (ref "R50") (pin "1") (pinfunction "1_1") (pintype "passive"))
    )
    (net (code "30") (name "Net-(LED2-K)") (class "Default")
      (node (ref "LED2") (pin "1") (pinfunction "K_1") (pintype "passive"))
      (node (ref "U2") (pin "4") (pinfunction "2Y_4") (pintype "passive"))
    )
    (net (code "31") (name "Net-(LED3-A)") (class "Default")
      (node (ref "LED3") (pin "2") (pinfunction "A_2") (pintype "passive"))
      (node (ref "R51") (pin "1") (pinfunction "1_1") (pintype "passive"))
    )
    (net (code "32") (name "Net-(LED3-K)") (class "Default")
      (node (ref "LED3") (pin "1") (pinfunction "K_1") (pintype "passive"))
      (node (ref "U2") (pin "6") (pinfunction "3Y_6") (pintype "passive"))
    )
    (net (code "33") (name "Net-(LED4-A)") (class "Default")
      (node (ref "LED4") (pin "2") (pinfunction "A_2") (pintype "passive"))
      (node (ref "R52") (pin "1") (pinfunction "1_1") (pintype "passive"))
    )
    (net (code "34") (name "Net-(LED4-K)") (class "Default")
      (node (ref "LED4") (pin "1") (pinfunction "K_1") (pintype "passive"))
      (node (ref "U2") (pin "8") (pinfunction "4Y_8") (pintype "passive"))
    )
    (net (code "35") (name "Net-(LED5-A)") (class "Default")
      (node (ref "LED5") (pin "2") (pinfunction "A_2") (pintype "passive"))
      (node (ref "R54") (pin "1") (pinfunction "1_1") (pintype "passive"))
    )
    (net (code "36") (name "Net-(LED5-K)") (class "Default")
      (node (ref "LED5") (pin "1") (pinfunction "K_1") (pintype "passive"))
      (node (ref "R71") (pin "2") (pinfunction "2_2") (pintype "passive"))
    )
    (net (code "37") (name "Net-(LED6-A)") (class "Default")
      (node (ref "LED6") (pin "2") (pinfunction "A_2") (pintype "passive"))
      (node (ref "R55") (pin "1") (pinfunction "1_1") (pintype "passive"))
    )
    (net (code "38") (name "Net-(LED6-K)") (class "Default")
      (node (ref "LED6") (pin "1") (pinfunction "K_1") (pintype "passive"))
      (node (ref "R72") (pin "2") (pinfunction "2_2") (pintype "passive"))
    )
    (net (code "39") (name "Net-(LED7-A)") (class "Default")
      (node (ref "LED7") (pin "2") (pinfunction "A_2") (pintype "passive"))
      (node (ref "R58") (pin "1") (pinfunction "1_1") (pintype "passive"))
    )
    (net (code "40") (name "Net-(LED7-K)") (class "Default")
      (node (ref "LED7") (pin "1") (pinfunction "K_1") (pintype "passive"))
      (node (ref "U1") (pin "18") (pinfunction "1Y1_18") (pintype "passive"))
    )
    (net (code "41") (name "Net-(LED8-A)") (class "Default")
      (node (ref "LED8") (pin "2") (pinfunction "A_2") (pintype "passive"))
      (node (ref "R59") (pin "1") (pinfunction "1_1") (pintype "passive"))
    )
    (net (code "42") (name "Net-(LED8-K)") (class "Default")
      (node (ref "LED8") (pin "1") (pinfunction "K_1") (pintype "passive"))
      (node (ref "U1") (pin "16") (pinfunction "1Y2_16") (pintype "passive"))
    )
    (net (code "43") (name "Net-(LED9-A)") (class "Default")
      (node (ref "LED9") (pin "2") (pinfunction "A_2") (pintype "passive"))
      (node (ref "R60") (pin "1") (pinfunction "1_1") (pintype "passive"))
    )
    (net (code "44") (name "Net-(LED9-K)") (class "Default")
      (node (ref "LED9") (pin "1") (pinfunction "K_1") (pintype "passive"))
      (node (ref "U1") (pin "14") (pinfunction "1Y3_14") (pintype "passive"))
    )
    (net (code "45") (name "Net-(LED10-A)") (class "Default")
      (node (ref "LED10") (pin "2") (pinfunction "A_2") (pintype "passive"))
      (node (ref "R61") (pin "1") (pinfunction "1_1") (pintype "passive"))
    )
    (net (code "46") (name "Net-(LED10-K)") (class "Default")
      (node (ref "LED10") (pin "1") (pinfunction "K_1") (pintype "passive"))
      (node (ref "U1") (pin "12") (pinfunction "1Y4_12") (pintype "passive"))
    )
    (net (code "47") (name "Net-(LED11-A)") (class "Default")
      (node (ref "LED11") (pin "2") (pinfunction "A_2") (pintype "passive"))
      (node (ref "R62") (pin "1") (pinfunction "1_1") (pintype "passive"))
    )
    (net (code "48") (name "Net-(LED11-K)") (class "Default")
      (node (ref "LED11") (pin "1") (pinfunction "K_1") (pintype "passive"))
      (node (ref "U1") (pin "9") (pinfunction "2Y1_9") (pintype "passive"))
    )
    (net (code "49") (name "Net-(LED12-A)") (class "Default")
      (node (ref "LED12") (pin "2") (pinfunction "A_2") (pintype "passive"))
      (node (ref "R63") (pin "1") (pinfunction "1_1") (pintype "passive"))
    )
    (net (code "50") (name "Net-(LED12-K)") (class "Default")
      (node (ref "LED12") (pin "1") (pinfunction "K_1") (pintype "passive"))
      (node (ref "U1") (pin "7") (pinfunction "2Y2_7") (pintype "passive"))
    )
    (net (code "51") (name "Net-(LED13-A)") (class "Default")
      (node (ref "LED13") (pin "2") (pinfunction "A_2") (pintype "passive"))
      (node (ref "R64") (pin "1") (pinfunction "1_1") (pintype "passive"))
    )
    (net (code "52") (name "Net-(LED13-K)") (class "Default")
      (node (ref "LED13") (pin "1") (pinfunction "K_1") (pintype "passive"))
      (node (ref "U1") (pin "5") (pinfunction "2Y3_5") (pintype "passive"))
    )
    (net (code "53") (name "Net-(LED14-A)") (class "Default")
      (node (ref "LED14") (pin "2") (pinfunction "A_2") (pintype "passive"))
      (node (ref "R65") (pin "1") (pinfunction "1_1") (pintype "passive"))
    )
    (net (code "54") (name "Net-(LED14-K)") (class "Default")
      (node (ref "LED14") (pin "1") (pinfunction "K_1") (pintype "passive"))
      (node (ref "U1") (pin "3") (pinfunction "2Y4_3") (pintype "passive"))
    )
    (net (code "55") (name "Net-(LED15-A)") (class "Default")
      (node (ref "LED15") (pin "2") (pinfunction "A_2") (pintype "passive"))
      (node (ref "R53") (pin "1") (pinfunction "1_1") (pintype "passive"))
    )
    (net (code "56") (name "Net-(LED15-K)") (class "Default")
      (node (ref "LED15") (pin "1") (pinfunction "K_1") (pintype "passive"))
      (node (ref "U2") (pin "12") (pinfunction "6Y_12") (pintype "passive"))
    )
    (net (code "57") (name "Net-(LED16-A)") (class "Default")
      (node (ref "LED16") (pin "2") (pinfunction "A_2") (pintype "passive"))
      (node (ref "R56") (pin "1") (pinfunction "1_1") (pintype "passive"))
    )
    (net (code "58") (name "Net-(LED17-A)") (class "Default")
      (node (ref "LED17") (pin "2") (pinfunction "A_2") (pintype "passive"))
      (node (ref "R57") (pin "2") (pinfunction "2_2") (pintype "passive"))
    )
    (net (code "59") (name "Net-(LED18-A)") (class "Default")
      (node (ref "LED18") (pin "2") (pinfunction "A_2") (pintype "passive"))
      (node (ref "R73") (pin "1") (pinfunction "1_1") (pintype "passive"))
    )
    (net (code "60") (name "Net-(LED18-K)") (class "Default")
      (node (ref "LED18") (pin "1") (pinfunction "K_1") (pintype "passive"))
      (node (ref "U3") (pin "2") (pinfunction "1Y_2") (pintype "passive"))
    )
    (net (code "61") (name "Net-(LED19-A)") (class "Default")
      (node (ref "LED19") (pin "2") (pinfunction "A_2") (pintype "passive"))
      (node (ref "R74") (pin "1") (pinfunction "1_1") (pintype "passive"))
    )
    (net (code "62") (name "Net-(LED19-K)") (class "Default")
      (node (ref "LED19") (pin "1") (pinfunction "K_1") (pintype "passive"))
      (node (ref "U3") (pin "4") (pinfunction "2Y_4") (pintype "passive"))
    )
    (net (code "63") (name "Net-(LED20-A)") (class "Default")
      (node (ref "LED20") (pin "2") (pinfunction "A_2") (pintype "passive"))
      (node (ref "R75") (pin "1") (pinfunction "1_1") (pintype "passive"))
    )
    (net (code "64") (name "Net-(LED20-K)") (class "Default")
      (node (ref "LED20") (pin "1") (pinfunction "K_1") (pintype "passive"))
      (node (ref "R95") (pin "2") (pinfunction "2_2") (pintype "passive"))
    )
    (net (code "65") (name "Net-(LED21-A)") (class "Default")
      (node (ref "LED21") (pin "2") (pinfunction "A_2") (pintype "passive"))
      (node (ref "R76") (pin "1") (pinfunction "1_1") (pintype "passive"))
    )
    (net (code "66") (name "Net-(LED21-K)") (class "Default")
      (node (ref "LED21") (pin "1") (pinfunction "K_1") (pintype "passive"))
      (node (ref "R96") (pin "2") (pinfunction "2_2") (pintype "passive"))
    )
    (net (code "67") (name "Net-(LED22-A)") (class "Default")
      (node (ref "LED22") (pin "2") (pinfunction "A_2") (pintype "passive"))
      (node (ref "R77") (pin "1") (pinfunction "1_1") (pintype "passive"))
    )
    (net (code "68") (name "Net-(LED22-K)") (class "Default")
      (node (ref "LED22") (pin "1") (pinfunction "K_1") (pintype "passive"))
      (node (ref "R97") (pin "2") (pinfunction "2_2") (pintype "passive"))
    )
    (net (code "69") (name "Net-(LED23-A)") (class "Default")
      (node (ref "LED23") (pin "2") (pinfunction "A_2") (pintype "passive"))
      (node (ref "R78") (pin "1") (pinfunction "1_1") (pintype "passive"))
    )
    (net (code "70") (name "Net-(LED23-K)") (class "Default")
      (node (ref "LED23") (pin "1") (pinfunction "K_1") (pintype "passive"))
      (node (ref "R98") (pin "2") (pinfunction "2_2") (pintype "passive"))
    )
    (net (code "71") (name "Net-(LED24-A)") (class "Default")
      (node (ref "LED24") (pin "2") (pinfunction "A_2") (pintype "passive"))
      (node (ref "R79") (pin "1") (pinfunction "1_1") (pintype "passive"))
    )
    (net (code "72") (name "Net-(LED24-K)") (class "Default")
      (node (ref "LED24") (pin "1") (pinfunction "K_1") (pintype "passive"))
      (node (ref "R92") (pin "2") (pinfunction "2_2") (pintype "passive"))
    )
    (net (code "73") (name "Net-(LED25-A)") (class "Default")
      (node (ref "LED25") (pin "2") (pinfunction "A_2") (pintype "passive"))
      (node (ref "R80") (pin "2") (pinfunction "2_2") (pintype "passive"))
    )
    (net (code "74") (name "Net-(LED25-K)") (class "Default")
      (node (ref "LED25") (pin "1") (pinfunction "K_1") (pintype "passive"))
      (node (ref "R93") (pin "2") (pinfunction "2_2") (pintype "passive"))
    )
    (net (code "75") (name "Net-(LED26-A)") (class "Default")
      (node (ref "LED26") (pin "2") (pinfunction "A_2") (pintype "passive"))
      (node (ref "R81") (pin "1") (pinfunction "1_1") (pintype "passive"))
    )
    (net (code "76") (name "Net-(LED26-K)") (class "Default")
      (node (ref "LED26") (pin "1") (pinfunction "K_1") (pintype "passive"))
      (node (ref "R94") (pin "2") (pinfunction "2_2") (pintype "passive"))
    )
    (net (code "77") (name "Net-(R84-Pad1)") (class "Default")
      (node (ref "R84") (pin "1") (pinfunction "1_1") (pintype "passive"))
      (node (ref "TP1") (pin "1") (pinfunction "1_1") (pintype "passive"))
    )
    (net (code "78") (name "Net-(R85-Pad2)") (class "Default")
      (node (ref "R85") (pin "2") (pinfunction "2_2") (pintype "passive"))
      (node (ref "TP2") (pin "1") (pinfunction "1_1") (pintype "passive"))
    )
    (net (code "79") (name "Net-(R86-Pad1)") (class "Default")
      (node (ref "R86") (pin "1") (pinfunction "1_1") (pintype "passive"))
      (node (ref "TP3") (pin "1") (pinfunction "1_1") (pintype "passive"))
    )
    (net (code "80") (name "Net-(R87-Pad2)") (class "Default")
      (node (ref "R87") (pin "2") (pinfunction "2_2") (pintype "passive"))
      (node (ref "TP4") (pin "1") (pinfunction "1_1") (pintype "passive"))
    )
    (net (code "81") (name "Net-(R88-Pad1)") (class "Default")
      (node (ref "R88") (pin "1") (pinfunction "1_1") (pintype "passive"))
      (node (ref "TP5") (pin "1") (pinfunction "1_1") (pintype "passive"))
    )
    (net (code "82") (name "Net-(R89-Pad2)") (class "Default")
      (node (ref "R89") (pin "2") (pinfunction "2_2") (pintype "passive"))
      (node (ref "TP6") (pin "1") (pinfunction "1_1") (pintype "passive"))
    )
    (net (code "83") (name "Net-(R90-Pad1)") (class "Default")
      (node (ref "R90") (pin "1") (pinfunction "1_1") (pintype "passive"))
      (node (ref "TP7") (pin "1") (pinfunction "1_1") (pintype "passive"))
    )
    (net (code "84") (name "Net-(R91-Pad2)") (class "Default")
      (node (ref "R91") (pin "2") (pinfunction "2_2") (pintype "passive"))
      (node (ref "TP8") (pin "1") (pinfunction "1_1") (pintype "passive"))
    )
    (net (code "85") (name "Net-(U2-1A)") (class "Default")
      (node (ref "R66") (pin "2") (pinfunction "2_2") (pintype "passive"))
      (node (ref "U2") (pin "1") (pinfunction "1A_1") (pintype "passive"))
    )
    (net (code "86") (name "Net-(U2-2A)") (class "Default")
      (node (ref "R67") (pin "2") (pinfunction "2_2") (pintype "passive"))
      (node (ref "U2") (pin "3") (pinfunction "2A_3") (pintype "passive"))
    )
    (net (code "87") (name "Net-(U2-3A)") (class "Default")
      (node (ref "R68") (pin "2") (pinfunction "2_2") (pintype "passive"))
      (node (ref "U2") (pin "5") (pinfunction "3A_5") (pintype "passive"))
    )
    (net (code "88") (name "Net-(U2-4A)") (class "Default")
      (node (ref "R69") (pin "2") (pinfunction "2_2") (pintype "passive"))
      (node (ref "U2") (pin "9") (pinfunction "4A_9") (pintype "passive"))
    )
    (net (code "89") (name "Net-(U2-5A)") (class "Default")
      (node (ref "R70") (pin "2") (pinfunction "2_2") (pintype "passive"))
      (node (ref "U2") (pin "11") (pinfunction "5A_11") (pintype "passive"))
    )
    (net (code "90") (name "Net-(U2-5Y)") (class "Default")
      (node (ref "U2") (pin "10") (pinfunction "5Y_10") (pintype "passive"))
      (node (ref "U2") (pin "13") (pinfunction "6A_13") (pintype "passive"))
    )
    (net (code "91") (name "Net-(U3-1A)") (class "Default")
      (node (ref "R82") (pin "2") (pinfunction "2_2") (pintype "passive"))
      (node (ref "U3") (pin "1") (pinfunction "1A_1") (pintype "passive"))
    )
    (net (code "92") (name "Net-(U3-2A)") (class "Default")
      (node (ref "R83") (pin "2") (pinfunction "2_2") (pintype "passive"))
      (node (ref "U3") (pin "3") (pinfunction "2A_3") (pintype "passive"))
    )
    (net (code "93") (name "Net-(U3-3A)") (class "Default")
      (node (ref "R84") (pin "2") (pinfunction "2_2") (pintype "passive"))
      (node (ref "U3") (pin "5") (pinfunction "3A_5") (pintype "passive"))
    )
    (net (code "94") (name "Net-(U3-3Y)") (class "Default")
      (node (ref "R85") (pin "1") (pinfunction "1_1") (pintype "passive"))
      (node (ref "U3") (pin "6") (pinfunction "3Y_6") (pintype "passive"))
    )
    (net (code "95") (name "Net-(U3-4A)") (class "Default")
      (node (ref "R86") (pin "2") (pinfunction "2_2") (pintype "passive"))
      (node (ref "U3") (pin "9") (pinfunction "4A_9") (pintype "passive"))
    )
    (net (code "96") (name "Net-(U3-4Y)") (class "Default")
      (node (ref "R87") (pin "1") (pinfunction "1_1") (pintype "passive"))
      (node (ref "U3") (pin "8") (pinfunction "4Y_8") (pintype "passive"))
    )
    (net (code "97") (name "Net-(U3-5A)") (class "Default")
      (node (ref "R88") (pin "2") (pinfunction "2_2") (pintype "passive"))
      (node (ref "U3") (pin "11") (pinfunction "5A_11") (pintype "passive"))
    )
    (net (code "98") (name "Net-(U3-5Y)") (class "Default")
      (node (ref "R89") (pin "1") (pinfunction "1_1") (pintype "passive"))
      (node (ref "U3") (pin "10") (pinfunction "5Y_10") (pintype "passive"))
    )
    (net (code "99") (name "Net-(U3-6A)") (class "Default")
      (node (ref "R90") (pin "2") (pinfunction "2_2") (pintype "passive"))
      (node (ref "U3") (pin "13") (pinfunction "6A_13") (pintype "passive"))
    )
    (net (code "100") (name "Net-(U3-6Y)") (class "Default")
      (node (ref "R91") (pin "1") (pinfunction "1_1") (pintype "passive"))
      (node (ref "U3") (pin "12") (pinfunction "6Y_12") (pintype "passive"))
    )
  )
)
